# Master_Controller.net
KiCad netlist of a schematic drawn in Altium Designer
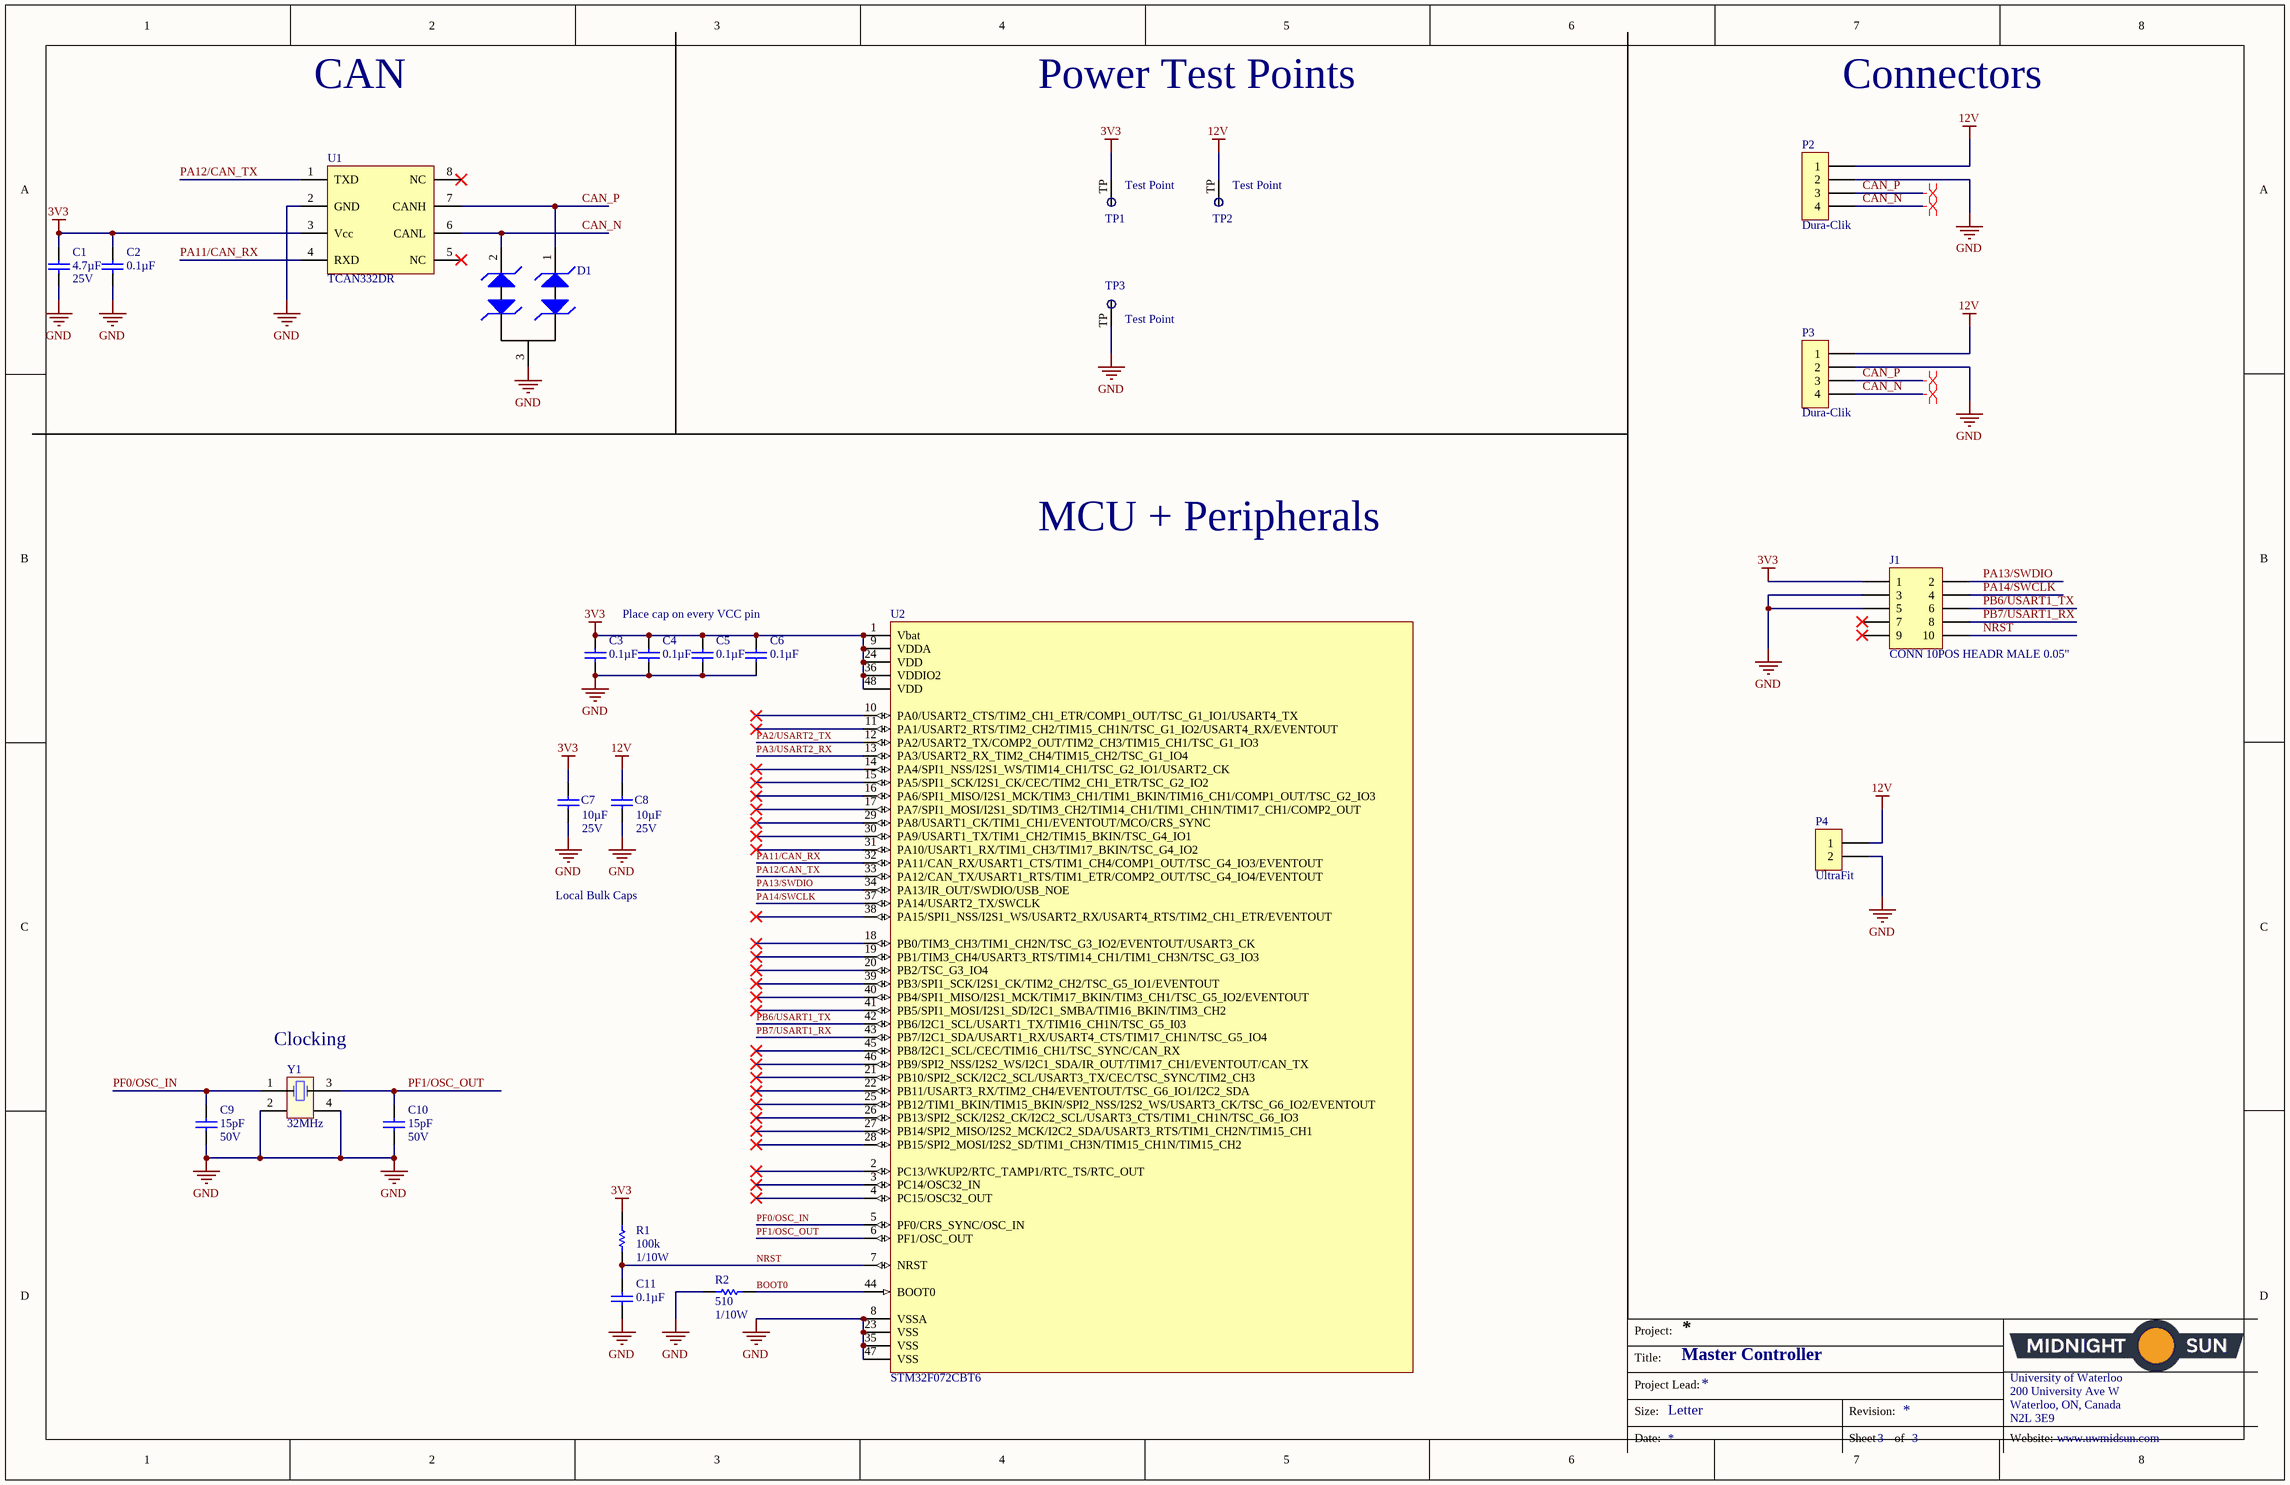
[diagram p0: Master_Controller.SchDoc]

(export (version "E")
  (design (tool "Eeschema 10.0.6"))
  (components
    (comp (ref "C1")
      (value "CAP CER 4.7UF 25V 10% X5R 0603")
      (footprint "CAP, 0603")
      (description "4.7µF ±10% 25V Ceramic Capacitor X5R 0603 (1608 Metric)")
      (fields
        (field (name "VOLTAGE") "25V")
        (field (name "TOLERANCE") "±10%")
        (field (name "CAPACITANCE") "4.7µF")
      )
      (libsource (lib "Schematic Diagrams") (part "CAP CER 4.7UF 25V 10% X5R 0603"))
    )
    (comp (ref "C2")
      (value "CAP CER 0.1UF 50V 10% X7R 0603")
      (footprint "CAP, 0603")
      (description "0.10µF ±10% 50V Ceramic Capacitor X7R 0603 (1608 Metric)")
      (fields
        (field (name "VOLTAGE") "50V")
        (field (name "TOLERANCE") "±10%")
        (field (name "CAPACITANCE") "0.1µF")
      )
      (libsource (lib "Schematic Diagrams") (part "CAP CER 0.1UF 50V 10% X7R 0603"))
    )
    (comp (ref "C3")
      (value "CAP CER 0.1UF 50V 10% X7R 0603")
      (footprint "CAP, 0603")
      (description "0.10µF ±10% 50V Ceramic Capacitor X7R 0603 (1608 Metric)")
      (fields
        (field (name "VOLTAGE") "50V")
        (field (name "TOLERANCE") "±10%")
        (field (name "CAPACITANCE") "0.1µF")
      )
      (libsource (lib "Schematic Diagrams") (part "CAP CER 0.1UF 50V 10% X7R 0603"))
    )
    (comp (ref "C4")
      (value "CAP CER 0.1UF 50V 10% X7R 0603")
      (footprint "CAP, 0603")
      (description "0.10µF ±10% 50V Ceramic Capacitor X7R 0603 (1608 Metric)")
      (fields
        (field (name "VOLTAGE") "50V")
        (field (name "TOLERANCE") "±10%")
        (field (name "CAPACITANCE") "0.1µF")
      )
      (libsource (lib "Schematic Diagrams") (part "CAP CER 0.1UF 50V 10% X7R 0603"))
    )
    (comp (ref "C5")
      (value "CAP CER 0.1UF 50V 10% X7R 0603")
      (footprint "CAP, 0603")
      (description "0.10µF ±10% 50V Ceramic Capacitor X7R 0603 (1608 Metric)")
      (fields
        (field (name "VOLTAGE") "50V")
        (field (name "TOLERANCE") "±10%")
        (field (name "CAPACITANCE") "0.1µF")
      )
      (libsource (lib "Schematic Diagrams") (part "CAP CER 0.1UF 50V 10% X7R 0603"))
    )
    (comp (ref "C6")
      (value "CAP CER 0.1UF 50V 10% X7R 0603")
      (footprint "CAP, 0603")
      (description "0.10µF ±10% 50V Ceramic Capacitor X7R 0603 (1608 Metric)")
      (fields
        (field (name "VOLTAGE") "50V")
        (field (name "TOLERANCE") "±10%")
        (field (name "CAPACITANCE") "0.1µF")
      )
      (libsource (lib "Schematic Diagrams") (part "CAP CER 0.1UF 50V 10% X7R 0603"))
    )
    (comp (ref "C7")
      (value "CAP CER 10uF 25V 10% X5R 0805")
      (footprint "CAP, 0805")
      (description "10µF ±10% 25V Ceramic Capacitor X5R 0805 (2012 Metric)")
      (fields
        (field (name "MANUFACTURER") "Murata Electronics North America")
        (field (name "MANUFACTURER PART NUMBER") "GRM21BR61E106KA73L")
        (field (name "VOLTAGE - RATED") "25V")
        (field (name "CAPACITANCE") "10µF")
      )
      (libsource (lib "Schematic Diagrams") (part "CAP CER 10uF 25V 10% X5R 0805"))
    )
    (comp (ref "C8")
      (value "CAP CER 10uF 25V 10% X5R 0805")
      (footprint "CAP, 0805")
      (description "10µF ±10% 25V Ceramic Capacitor X5R 0805 (2012 Metric)")
      (fields
        (field (name "MANUFACTURER") "Murata Electronics North America")
        (field (name "MANUFACTURER PART NUMBER") "GRM21BR61E106KA73L")
        (field (name "VOLTAGE - RATED") "25V")
        (field (name "CAPACITANCE") "10µF")
      )
      (libsource (lib "Schematic Diagrams") (part "CAP CER 10uF 25V 10% X5R 0805"))
    )
    (comp (ref "C9")
      (value "CAP CER 15PF 50V ±5% NPO 0603")
      (footprint "CAP, 0603")
      (description "15pF ±5% 50V Ceramic Capacitor C0G, NP0 0603 (1608 Metric)")
      (fields
        (field (name "VOLTAGE") "50V")
        (field (name "TOLERANCE") "±5%")
        (field (name "CAPACITANCE") "15pF")
      )
      (libsource (lib "Schematic Diagrams") (part "CAP CER 15PF 50V ±5% NPO 0603"))
    )
    (comp (ref "C10")
      (value "CAP CER 15PF 50V ±5% NPO 0603")
      (footprint "CAP, 0603")
      (description "15pF ±5% 50V Ceramic Capacitor C0G, NP0 0603 (1608 Metric)")
      (fields
        (field (name "VOLTAGE") "50V")
        (field (name "TOLERANCE") "±5%")
        (field (name "CAPACITANCE") "15pF")
      )
      (libsource (lib "Schematic Diagrams") (part "CAP CER 15PF 50V ±5% NPO 0603"))
    )
    (comp (ref "C11")
      (value "CAP CER 0.1UF 50V 10% X7R 0603")
      (footprint "CAP, 0603")
      (description "0.10µF ±10% 50V Ceramic Capacitor X7R 0603 (1608 Metric)")
      (fields
        (field (name "VOLTAGE") "50V")
        (field (name "TOLERANCE") "±10%")
        (field (name "CAPACITANCE") "0.1µF")
      )
      (libsource (lib "Schematic Diagrams") (part "CAP CER 0.1UF 50V 10% X7R 0603"))
    )
    (comp (ref "D1")
      (value "DIODE TVS 24VWM 70VC SOT23")
      (footprint "SOT23")
      (description "TVS DIODE 24VWM 70VC SOT23")
      (libsource (lib "Schematic Diagrams") (part "DIODE TVS 24VWM 70VC SOT23"))
    )
    (comp (ref "J1")
      (value "CONN 10POS HEADR MALE 0.05\"")
      (footprint "CONN, 10POS 0.05\" Debug Header")
      (description "10 Positions Header Connector 0.050\" (1.27mm) Surface Mount Gold")
      (libsource (lib "Schematic Diagrams") (part "CONN 10POS HEADR MALE 0.05{dblquote}"))
    )
    (comp (ref "P2")
      (value "Dura-Clik")
      (footprint "CONN, 4POS DURA-CLIK VERT")
      (description "4 Positions Header Connector 0.079\" (2.00mm) Surface Mount Tin")
      (fields
        (field (name "MANUFACTURER") "Molex, LLC")
        (field (name "MANUFACTURER PART NUMBER") "5600200420")
      )
      (libsource (lib "Schematic Diagrams") (part "CONN 4POS DURA-CLIK 0.079{dblquote}"))
    )
    (comp (ref "P3")
      (value "Dura-Clik")
      (footprint "CONN, 4POS DURA-CLIK VERT")
      (description "4 Positions Header Connector 0.079\" (2.00mm) Surface Mount Tin")
      (fields
        (field (name "MANUFACTURER") "Molex, LLC")
        (field (name "MANUFACTURER PART NUMBER") "5600200420")
      )
      (libsource (lib "Schematic Diagrams") (part "CONN 4POS DURA-CLIK 0.079{dblquote}"))
    )
    (comp (ref "P4")
      (value "CONN 2POS ULTRA-FIT 0.138\"")
      (footprint "CONN, 2POS ULTRA-FIT")
      (description "2 Positions Header, Shrouded Connector 0.138\" (3.50mm) Through Hole Gold")
      (fields (field (name "VOLTAGE") "400V") (field (name "SERIES") "UltraFit"))
      (libsource (lib "Schematic Diagrams") (part "CONN 2POS ULTRA-FIT 0.138{dblquote}"))
    )
    (comp (ref "R1")
      (value "RES 100K OHM 5% 1/8W 0603")
      (footprint "RES, 0603")
      (description "RES SMD 100K OHM 5% 1/10W 0603")
      (fields
        (field (name "TOLERANCE") "±5%")
        (field (name "RESISTANCE") "100k")
        (field (name "POWER") "1/10W")
      )
      (libsource (lib "Schematic Diagrams") (part "RES 100K OHM 5% 1/8W 0603"))
    )
    (comp (ref "R2")
      (value "RES 510 OHM 5% 1/10W 0603")
      (footprint "RES, 0603")
      (description "RES SMD 510 OHM 5% 1/10W 0603")
      (fields
        (field (name "TOLERANCE") "±5%")
        (field (name "RESISTANCE") "510")
        (field (name "POWER") "1/10W")
      )
      (libsource (lib "Schematic Diagrams") (part "RES 510 OHM 5% 1/10W 0603"))
    )
    (comp (ref "TP1")
      (value "Test Point")
      (footprint "Test Point")
      (libsource (lib "Schematic Diagrams") (part "Test Point"))
    )
    (comp (ref "TP2")
      (value "Test Point")
      (footprint "Test Point")
      (libsource (lib "Schematic Diagrams") (part "Test Point"))
    )
    (comp (ref "TP3")
      (value "Test Point")
      (footprint "Test Point")
      (libsource (lib "Schematic Diagrams") (part "Test Point"))
    )
    (comp (ref "U1")
      (value "IC CAN Tranceiver TCAN332DR")
      (footprint "TSOP65P280X145-8N")
      (description "1/1 Transceiver CAN 8-SOIC")
      (fields
        (field (name "MANUFACTURER PART NUMBER") "TCAN332DR")
        (field (name "DIGIKEY PART NUMBER") "296-43711-1-ND")
      )
      (libsource (lib "Schematic Diagrams") (part "IC CAN Tranceiver TCAN332DR"))
    )
    (comp (ref "U2")
      (value "IC MCU 32BIT 128KB FLASH 48LQFP")
      (footprint "TSQFP50P890X890X160-48M")
      (description "ARM® Cortex®-M0 STM32 F0 Microcontroller IC 32-Bit 48MHz 128KB (128K x 8) FLASH 48-LQFP (7x7)")
      (fields (field (name "MANUFACTURER PART NUMBER 1") "STM32F072CBT6"))
      (libsource (lib "Schematic Diagrams") (part "IC MCU 32BIT 128KB FLASH 48LQFP"))
    )
    (comp (ref "Y1")
      (value "CRYSTAL 32 MHz 8pF 4-SMD")
      (footprint "CX2520DB CRYSTAL")
      (description "32MHz ±15ppm Crystal 8pF 50 Ohm -40°C ~ 85°C AEC-Q200 Surface Mount 4-SMD, No Lead")
      (fields (field (name "FREQUENCY") "32MHz"))
      (libsource (lib "Schematic Diagrams") (part "CRYSTAL 32 MHz 8pF 4-SMD"))
    )
  )
  (nets
    (net (code "1") (name "/BOOT0") (class "Default")
      (node (ref "R2") (pin "2") (pinfunction "2_2") (pintype "passive"))
      (node (ref "U2") (pin "44") (pinfunction "BOOT0_44") (pintype "input"))
    )
    (net (code "2") (name "/CAN_N") (class "Default")
      (node (ref "D1") (pin "2") (pinfunction "Cathode2_2") (pintype "passive"))
      (node (ref "P2") (pin "4") (pinfunction "4_4") (pintype "passive"))
      (node (ref "P3") (pin "4") (pinfunction "4_4") (pintype "passive"))
      (node (ref "U1") (pin "6") (pinfunction "CANL_6") (pintype "passive"))
    )
    (net (code "3") (name "/CAN_P") (class "Default")
      (node (ref "D1") (pin "1") (pinfunction "Cathode1_1") (pintype "passive"))
      (node (ref "P2") (pin "3") (pinfunction "3_3") (pintype "passive"))
      (node (ref "P3") (pin "3") (pinfunction "3_3") (pintype "passive"))
      (node (ref "U1") (pin "7") (pinfunction "CANH_7") (pintype "passive"))
    )
    (net (code "4") (name "/NRST") (class "Default")
      (node (ref "C11") (pin "2") (pinfunction "2_2") (pintype "passive"))
      (node (ref "J1") (pin "10") (pinfunction "10_10") (pintype "passive"))
      (node (ref "R1") (pin "1") (pinfunction "1_1") (pintype "passive"))
      (node (ref "U2") (pin "7") (pinfunction "NRST_7") (pintype "bidirectional"))
    )
    (net (code "5") (name "/PA2{slash}USART2_TX") (class "Default")
      (node (ref "U2") (pin "12") (pinfunction "PA2/USART2_TX/COMP2_OUT/TIM2_CH3/TIM15_CH1/TSC_G1_IO3_12") (pintype "bidirectional"))
    )
    (net (code "6") (name "/PA3{slash}USART2_RX") (class "Default")
      (node (ref "U2") (pin "13") (pinfunction "PA3/USART2_RX_TIM2_CH4/TIM15_CH2/TSC_G1_IO4_13") (pintype "bidirectional"))
    )
    (net (code "7") (name "/PA11{slash}CAN_RX") (class "Default")
      (node (ref "U1") (pin "4") (pinfunction "RXD_4") (pintype "passive"))
      (node (ref "U2") (pin "32") (pinfunction "PA11/CAN_RX/USART1_CTS/TIM1_CH4/COMP1_OUT/TSC_G4_IO3/EVENTOUT_32") (pintype "bidirectional"))
    )
    (net (code "8") (name "/PA12{slash}CAN_TX") (class "Default")
      (node (ref "U1") (pin "1") (pinfunction "TXD_1") (pintype "passive"))
      (node (ref "U2") (pin "33") (pinfunction "PA12/CAN_TX/USART1_RTS/TIM1_ETR/COMP2_OUT/TSC_G4_IO4/EVENTOUT_33") (pintype "bidirectional"))
    )
    (net (code "9") (name "/PA13{slash}SWDIO") (class "Default")
      (node (ref "J1") (pin "2") (pinfunction "2_2") (pintype "passive"))
      (node (ref "U2") (pin "34") (pinfunction "PA13/IR_OUT/SWDIO/USB_NOE_34") (pintype "bidirectional"))
    )
    (net (code "10") (name "/PA14{slash}SWCLK") (class "Default")
      (node (ref "J1") (pin "4") (pinfunction "4_4") (pintype "passive"))
      (node (ref "U2") (pin "37") (pinfunction "PA14/USART2_TX/SWCLK_37") (pintype "bidirectional"))
    )
    (net (code "11") (name "/PB6{slash}USART1_TX") (class "Default")
      (node (ref "J1") (pin "6") (pinfunction "6_6") (pintype "passive"))
      (node (ref "U2") (pin "42") (pinfunction "PB6/I2C1_SCL/USART1_TX/TIM16_CH1N/TSC_G5_I03_42") (pintype "bidirectional"))
    )
    (net (code "12") (name "/PB7{slash}USART1_RX") (class "Default")
      (node (ref "J1") (pin "8") (pinfunction "8_8") (pintype "passive"))
      (node (ref "U2") (pin "43") (pinfunction "PB7/I2C1_SDA/USART1_RX/USART4_CTS/TIM17_CH1N/TSC_G5_IO4_43") (pintype "bidirectional"))
    )
    (net (code "13") (name "/PF0{slash}OSC_IN") (class "Default")
      (node (ref "C9") (pin "2") (pinfunction "2_2") (pintype "passive"))
      (node (ref "U2") (pin "5") (pinfunction "PF0/CRS_SYNC/OSC_IN_5") (pintype "bidirectional"))
      (node (ref "Y1") (pin "1") (pinfunction "OSC1_1") (pintype "passive"))
    )
    (net (code "14") (name "/PF1{slash}OSC_OUT") (class "Default")
      (node (ref "C10") (pin "2") (pinfunction "2_2") (pintype "passive"))
      (node (ref "U2") (pin "6") (pinfunction "PF1/OSC_OUT_6") (pintype "bidirectional"))
      (node (ref "Y1") (pin "3") (pinfunction "OSC2_3") (pintype "passive"))
    )
    (net (code "15") (name "3V3") (class "Default")
      (node (ref "C1") (pin "2") (pinfunction "2_2") (pintype "passive"))
      (node (ref "C2") (pin "2") (pinfunction "2_2") (pintype "passive"))
      (node (ref "C3") (pin "2") (pinfunction "2_2") (pintype "passive"))
      (node (ref "C4") (pin "2") (pinfunction "2_2") (pintype "passive"))
      (node (ref "C5") (pin "2") (pinfunction "2_2") (pintype "passive"))
      (node (ref "C6") (pin "2") (pinfunction "2_2") (pintype "passive"))
      (node (ref "C7") (pin "1") (pinfunction "1_1") (pintype "passive"))
      (node (ref "J1") (pin "1") (pinfunction "1_1") (pintype "passive"))
      (node (ref "R1") (pin "2") (pinfunction "2_2") (pintype "passive"))
      (node (ref "TP1") (pin "TP") (pinfunction "1_TP") (pintype "passive"))
      (node (ref "U1") (pin "3") (pinfunction "Vcc_3") (pintype "passive"))
      (node (ref "U2") (pin "1") (pinfunction "Vbat_1") (pintype "power_in"))
      (node (ref "U2") (pin "24") (pinfunction "VDD_24") (pintype "power_in"))
      (node (ref "U2") (pin "36") (pinfunction "VDDIO2_36") (pintype "power_in"))
      (node (ref "U2") (pin "48") (pinfunction "VDD_48") (pintype "power_in"))
      (node (ref "U2") (pin "9") (pinfunction "VDDA_9") (pintype "power_in"))
    )
    (net (code "16") (name "12V") (class "Default")
      (node (ref "C8") (pin "1") (pinfunction "1_1") (pintype "passive"))
      (node (ref "P2") (pin "1") (pinfunction "1_1") (pintype "passive"))
      (node (ref "P3") (pin "1") (pinfunction "1_1") (pintype "passive"))
      (node (ref "P4") (pin "1") (pinfunction "1_1") (pintype "passive"))
      (node (ref "TP2") (pin "TP") (pinfunction "1_TP") (pintype "passive"))
    )
    (net (code "17") (name "GND") (class "Default")
      (node (ref "C1") (pin "1") (pinfunction "1_1") (pintype "passive"))
      (node (ref "C10") (pin "1") (pinfunction "1_1") (pintype "passive"))
      (node (ref "C11") (pin "1") (pinfunction "1_1") (pintype "passive"))
      (node (ref "C2") (pin "1") (pinfunction "1_1") (pintype "passive"))
      (node (ref "C3") (pin "1") (pinfunction "1_1") (pintype "passive"))
      (node (ref "C4") (pin "1") (pinfunction "1_1") (pintype "passive"))
      (node (ref "C5") (pin "1") (pinfunction "1_1") (pintype "passive"))
      (node (ref "C6") (pin "1") (pinfunction "1_1") (pintype "passive"))
      (node (ref "C7") (pin "2") (pinfunction "2_2") (pintype "passive"))
      (node (ref "C8") (pin "2") (pinfunction "2_2") (pintype "passive"))
      (node (ref "C9") (pin "1") (pinfunction "1_1") (pintype "passive"))
      (node (ref "D1") (pin "3") (pinfunction "Common_Cathode_3") (pintype "power_in"))
      (node (ref "J1") (pin "3") (pinfunction "3_3") (pintype "passive"))
      (node (ref "J1") (pin "5") (pinfunction "5_5") (pintype "passive"))
      (node (ref "P2") (pin "2") (pinfunction "2_2") (pintype "passive"))
      (node (ref "P3") (pin "2") (pinfunction "2_2") (pintype "passive"))
      (node (ref "P4") (pin "2") (pinfunction "2_2") (pintype "passive"))
      (node (ref "R2") (pin "1") (pinfunction "1_1") (pintype "passive"))
      (node (ref "TP3") (pin "TP") (pinfunction "1_TP") (pintype "passive"))
      (node (ref "U1") (pin "2") (pinfunction "GND_2") (pintype "passive"))
      (node (ref "U2") (pin "23") (pinfunction "VSS_23") (pintype "power_in"))
      (node (ref "U2") (pin "35") (pinfunction "VSS_35") (pintype "power_in"))
      (node (ref "U2") (pin "47") (pinfunction "VSS_47") (pintype "power_in"))
      (node (ref "U2") (pin "8") (pinfunction "VSSA_8") (pintype "power_in"))
      (node (ref "Y1") (pin "2") (pinfunction "2_2") (pintype "passive"))
      (node (ref "Y1") (pin "4") (pinfunction "3_4") (pintype "passive"))
    )
    (net (code "18") (name "unconnected-(J1-Pad7)") (class "Default")
      (node (ref "J1") (pin "7") (pinfunction "7_7") (pintype "passive+no_connect"))
    )
    (net (code "19") (name "unconnected-(J1-Pad9)") (class "Default")
      (node (ref "J1") (pin "9") (pinfunction "9_9") (pintype "passive+no_connect"))
    )
    (net (code "20") (name "unconnected-(U1-NC-Pad5)") (class "Default")
      (node (ref "U1") (pin "5") (pinfunction "NC_5") (pintype "passive+no_connect"))
    )
    (net (code "21") (name "unconnected-(U1-NC-Pad8)") (class "Default")
      (node (ref "U1") (pin "8") (pinfunction "NC_8") (pintype "passive+no_connect"))
    )
    (net (code "22") (name "unconnected-(U2-PA0{slash}USART2_CTS{slash}TIM2_CH1_ETR{slash}COMP1_OUT{slash}TSC_G1_IO1{slash}USART4_TX-Pad10)") (class "Default")
      (node (ref "U2") (pin "10") (pinfunction "PA0/USART2_CTS/TIM2_CH1_ETR/COMP1_OUT/TSC_G1_IO1/USART4_TX_10") (pintype "bidirectional+no_connect"))
    )
    (net (code "23") (name "unconnected-(U2-PA1{slash}USART2_RTS{slash}TIM2_CH2{slash}TIM15_CH1N{slash}TSC_G1_IO2{slash}USART4_RX{slash}EVENTOUT-Pad11)") (class "Default")
      (node (ref "U2") (pin "11") (pinfunction "PA1/USART2_RTS/TIM2_CH2/TIM15_CH1N/TSC_G1_IO2/USART4_RX/EVENTOUT_11") (pintype "bidirectional+no_connect"))
    )
    (net (code "24") (name "unconnected-(U2-PA4{slash}SPI1_NSS{slash}I2S1_WS{slash}TIM14_CH1{slash}TSC_G2_IO1{slash}USART2_CK-Pad14)") (class "Default")
      (node (ref "U2") (pin "14") (pinfunction "PA4/SPI1_NSS/I2S1_WS/TIM14_CH1/TSC_G2_IO1/USART2_CK_14") (pintype "bidirectional+no_connect"))
    )
    (net (code "25") (name "unconnected-(U2-PA5{slash}SPI1_SCK{slash}I2S1_CK{slash}CEC{slash}TIM2_CH1_ETR{slash}TSC_G2_IO2-Pad15)") (class "Default")
      (node (ref "U2") (pin "15") (pinfunction "PA5/SPI1_SCK/I2S1_CK/CEC/TIM2_CH1_ETR/TSC_G2_IO2_15") (pintype "bidirectional+no_connect"))
    )
    (net (code "26") (name "unconnected-(U2-PA6{slash}SPI1_MISO{slash}I2S1_MCK{slash}TIM3_CH1{slash}TIM1_BKIN{slash}TIM16_CH1{slash}COMP1_OUT{slash}TSC_G2_IO3-Pad16)") (class "Default")
      (node (ref "U2") (pin "16") (pinfunction "PA6/SPI1_MISO/I2S1_MCK/TIM3_CH1/TIM1_BKIN/TIM16_CH1/COMP1_OUT/TSC_G2_IO3_16") (pintype "bidirectional+no_connect"))
    )
    (net (code "27") (name "unconnected-(U2-PA7{slash}SPI1_MOSI{slash}I2S1_SD{slash}TIM3_CH2{slash}TIM14_CH1{slash}TIM1_CH1N{slash}TIM17_CH1{slash}COMP2_OUT-Pad17)") (class "Default")
      (node (ref "U2") (pin "17") (pinfunction "PA7/SPI1_MOSI/I2S1_SD/TIM3_CH2/TIM14_CH1/TIM1_CH1N/TIM17_CH1/COMP2_OUT_17") (pintype "bidirectional+no_connect"))
    )
    (net (code "28") (name "unconnected-(U2-PA8{slash}USART1_CK{slash}TIM1_CH1{slash}EVENTOUT{slash}MCO{slash}CRS_SYNC-Pad29)") (class "Default")
      (node (ref "U2") (pin "29") (pinfunction "PA8/USART1_CK/TIM1_CH1/EVENTOUT/MCO/CRS_SYNC_29") (pintype "bidirectional+no_connect"))
    )
    (net (code "29") (name "unconnected-(U2-PA9{slash}USART1_TX{slash}TIM1_CH2{slash}TIM15_BKIN{slash}TSC_G4_IO1-Pad30)") (class "Default")
      (node (ref "U2") (pin "30") (pinfunction "PA9/USART1_TX/TIM1_CH2/TIM15_BKIN/TSC_G4_IO1_30") (pintype "bidirectional+no_connect"))
    )
    (net (code "30") (name "unconnected-(U2-PA10{slash}USART1_RX{slash}TIM1_CH3{slash}TIM17_BKIN{slash}TSC_G4_IO2-Pad31)") (class "Default")
      (node (ref "U2") (pin "31") (pinfunction "PA10/USART1_RX/TIM1_CH3/TIM17_BKIN/TSC_G4_IO2_31") (pintype "bidirectional+no_connect"))
    )
    (net (code "31") (name "unconnected-(U2-PA15{slash}SPI1_NSS{slash}I2S1_WS{slash}USART2_RX{slash}USART4_RTS{slash}TIM2_CH1_ETR{slash}EVENTOUT-Pad38)") (class "Default")
      (node (ref "U2") (pin "38") (pinfunction "PA15/SPI1_NSS/I2S1_WS/USART2_RX/USART4_RTS/TIM2_CH1_ETR/EVENTOUT_38") (pintype "bidirectional+no_connect"))
    )
    (net (code "32") (name "unconnected-(U2-PB0{slash}TIM3_CH3{slash}TIM1_CH2N{slash}TSC_G3_IO2{slash}EVENTOUT{slash}USART3_CK-Pad18)") (class "Default")
      (node (ref "U2") (pin "18") (pinfunction "PB0/TIM3_CH3/TIM1_CH2N/TSC_G3_IO2/EVENTOUT/USART3_CK_18") (pintype "bidirectional+no_connect"))
    )
    (net (code "33") (name "unconnected-(U2-PB1{slash}TIM3_CH4{slash}USART3_RTS{slash}TIM14_CH1{slash}TIM1_CH3N{slash}TSC_G3_IO3-Pad19)") (class "Default")
      (node (ref "U2") (pin "19") (pinfunction "PB1/TIM3_CH4/USART3_RTS/TIM14_CH1/TIM1_CH3N/TSC_G3_IO3_19") (pintype "bidirectional+no_connect"))
    )
    (net (code "34") (name "unconnected-(U2-PB2{slash}TSC_G3_IO4-Pad20)") (class "Default")
      (node (ref "U2") (pin "20") (pinfunction "PB2/TSC_G3_IO4_20") (pintype "bidirectional+no_connect"))
    )
    (net (code "35") (name "unconnected-(U2-PB3{slash}SPI1_SCK{slash}I2S1_CK{slash}TIM2_CH2{slash}TSC_G5_IO1{slash}EVENTOUT-Pad39)") (class "Default")
      (node (ref "U2") (pin "39") (pinfunction "PB3/SPI1_SCK/I2S1_CK/TIM2_CH2/TSC_G5_IO1/EVENTOUT_39") (pintype "bidirectional+no_connect"))
    )
    (net (code "36") (name "unconnected-(U2-PB4{slash}SPI1_MISO{slash}I2S1_MCK{slash}TIM17_BKIN{slash}TIM3_CH1{slash}TSC_G5_IO2{slash}EVENTOUT-Pad40)") (class "Default")
      (node (ref "U2") (pin "40") (pinfunction "PB4/SPI1_MISO/I2S1_MCK/TIM17_BKIN/TIM3_CH1/TSC_G5_IO2/EVENTOUT_40") (pintype "bidirectional+no_connect"))
    )
    (net (code "37") (name "unconnected-(U2-PB5{slash}SPI1_MOSI{slash}I2S1_SD{slash}I2C1_SMBA{slash}TIM16_BKIN{slash}TIM3_CH2-Pad41)") (class "Default")
      (node (ref "U2") (pin "41") (pinfunction "PB5/SPI1_MOSI/I2S1_SD/I2C1_SMBA/TIM16_BKIN/TIM3_CH2_41") (pintype "bidirectional+no_connect"))
    )
    (net (code "38") (name "unconnected-(U2-PB8{slash}I2C1_SCL{slash}CEC{slash}TIM16_CH1{slash}TSC_SYNC{slash}CAN_RX-Pad45)") (class "Default")
      (node (ref "U2") (pin "45") (pinfunction "PB8/I2C1_SCL/CEC/TIM16_CH1/TSC_SYNC/CAN_RX_45") (pintype "bidirectional+no_connect"))
    )
    (net (code "39") (name "unconnected-(U2-PB9{slash}SPI2_NSS{slash}I2S2_WS{slash}I2C1_SDA{slash}IR_OUT{slash}TIM17_CH1{slash}EVENTOUT{slash}CAN_TX-Pad46)") (class "Default")
      (node (ref "U2") (pin "46") (pinfunction "PB9/SPI2_NSS/I2S2_WS/I2C1_SDA/IR_OUT/TIM17_CH1/EVENTOUT/CAN_TX_46") (pintype "bidirectional+no_connect"))
    )
    (net (code "40") (name "unconnected-(U2-PB10{slash}SPI2_SCK{slash}I2C2_SCL{slash}USART3_TX{slash}CEC{slash}TSC_SYNC{slash}TIM2_CH3-Pad21)") (class "Default")
      (node (ref "U2") (pin "21") (pinfunction "PB10/SPI2_SCK/I2C2_SCL/USART3_TX/CEC/TSC_SYNC/TIM2_CH3_21") (pintype "bidirectional+no_connect"))
    )
    (net (code "41") (name "unconnected-(U2-PB11{slash}USART3_RX{slash}TIM2_CH4{slash}EVENTOUT{slash}TSC_G6_IO1{slash}I2C2_SDA-Pad22)") (class "Default")
      (node (ref "U2") (pin "22") (pinfunction "PB11/USART3_RX/TIM2_CH4/EVENTOUT/TSC_G6_IO1/I2C2_SDA_22") (pintype "bidirectional+no_connect"))
    )
    (net (code "42") (name "unconnected-(U2-PB12{slash}TIM1_BKIN{slash}TIM15_BKIN{slash}SPI2_NSS{slash}I2S2_WS{slash}USART3_CK{slash}TSC_G6_IO2{slash}EVENTOUT-Pad25)") (class "Default")
      (node (ref "U2") (pin "25") (pinfunction "PB12/TIM1_BKIN/TIM15_BKIN/SPI2_NSS/I2S2_WS/USART3_CK/TSC_G6_IO2/EVENTOUT_25") (pintype "bidirectional+no_connect"))
    )
    (net (code "43") (name "unconnected-(U2-PB13{slash}SPI2_SCK{slash}I2S2_CK{slash}I2C2_SCL{slash}USART3_CTS{slash}TIM1_CH1N{slash}TSC_G6_IO3-Pad26)") (class "Default")
      (node (ref "U2") (pin "26") (pinfunction "PB13/SPI2_SCK/I2S2_CK/I2C2_SCL/USART3_CTS/TIM1_CH1N/TSC_G6_IO3_26") (pintype "bidirectional+no_connect"))
    )
    (net (code "44") (name "unconnected-(U2-PB14{slash}SPI2_MISO{slash}I2S2_MCK{slash}I2C2_SDA{slash}USART3_RTS{slash}TIM1_CH2N{slash}TIM15_CH1-Pad27)") (class "Default")
      (node (ref "U2") (pin "27") (pinfunction "PB14/SPI2_MISO/I2S2_MCK/I2C2_SDA/USART3_RTS/TIM1_CH2N/TIM15_CH1_27") (pintype "bidirectional+no_connect"))
    )
    (net (code "45") (name "unconnected-(U2-PB15{slash}SPI2_MOSI{slash}I2S2_SD{slash}TIM1_CH3N{slash}TIM15_CH1N{slash}TIM15_CH2-Pad28)") (class "Default")
      (node (ref "U2") (pin "28") (pinfunction "PB15/SPI2_MOSI/I2S2_SD/TIM1_CH3N/TIM15_CH1N/TIM15_CH2_28") (pintype "bidirectional+no_connect"))
    )
    (net (code "46") (name "unconnected-(U2-PC13{slash}WKUP2{slash}RTC_TAMP1{slash}RTC_TS{slash}RTC_OUT-Pad2)") (class "Default")
      (node (ref "U2") (pin "2") (pinfunction "PC13/WKUP2/RTC_TAMP1/RTC_TS/RTC_OUT_2") (pintype "bidirectional+no_connect"))
    )
    (net (code "47") (name "unconnected-(U2-PC14{slash}OSC32_IN-Pad3)") (class "Default")
      (node (ref "U2") (pin "3") (pinfunction "PC14/OSC32_IN_3") (pintype "bidirectional+no_connect"))
    )
    (net (code "48") (name "unconnected-(U2-PC15{slash}OSC32_OUT-Pad4)") (class "Default")
      (node (ref "U2") (pin "4") (pinfunction "PC15/OSC32_OUT_4") (pintype "bidirectional+no_connect"))
    )
  )
)
